# main.net
KiCad netlist of a schematic drawn in Altium Designer
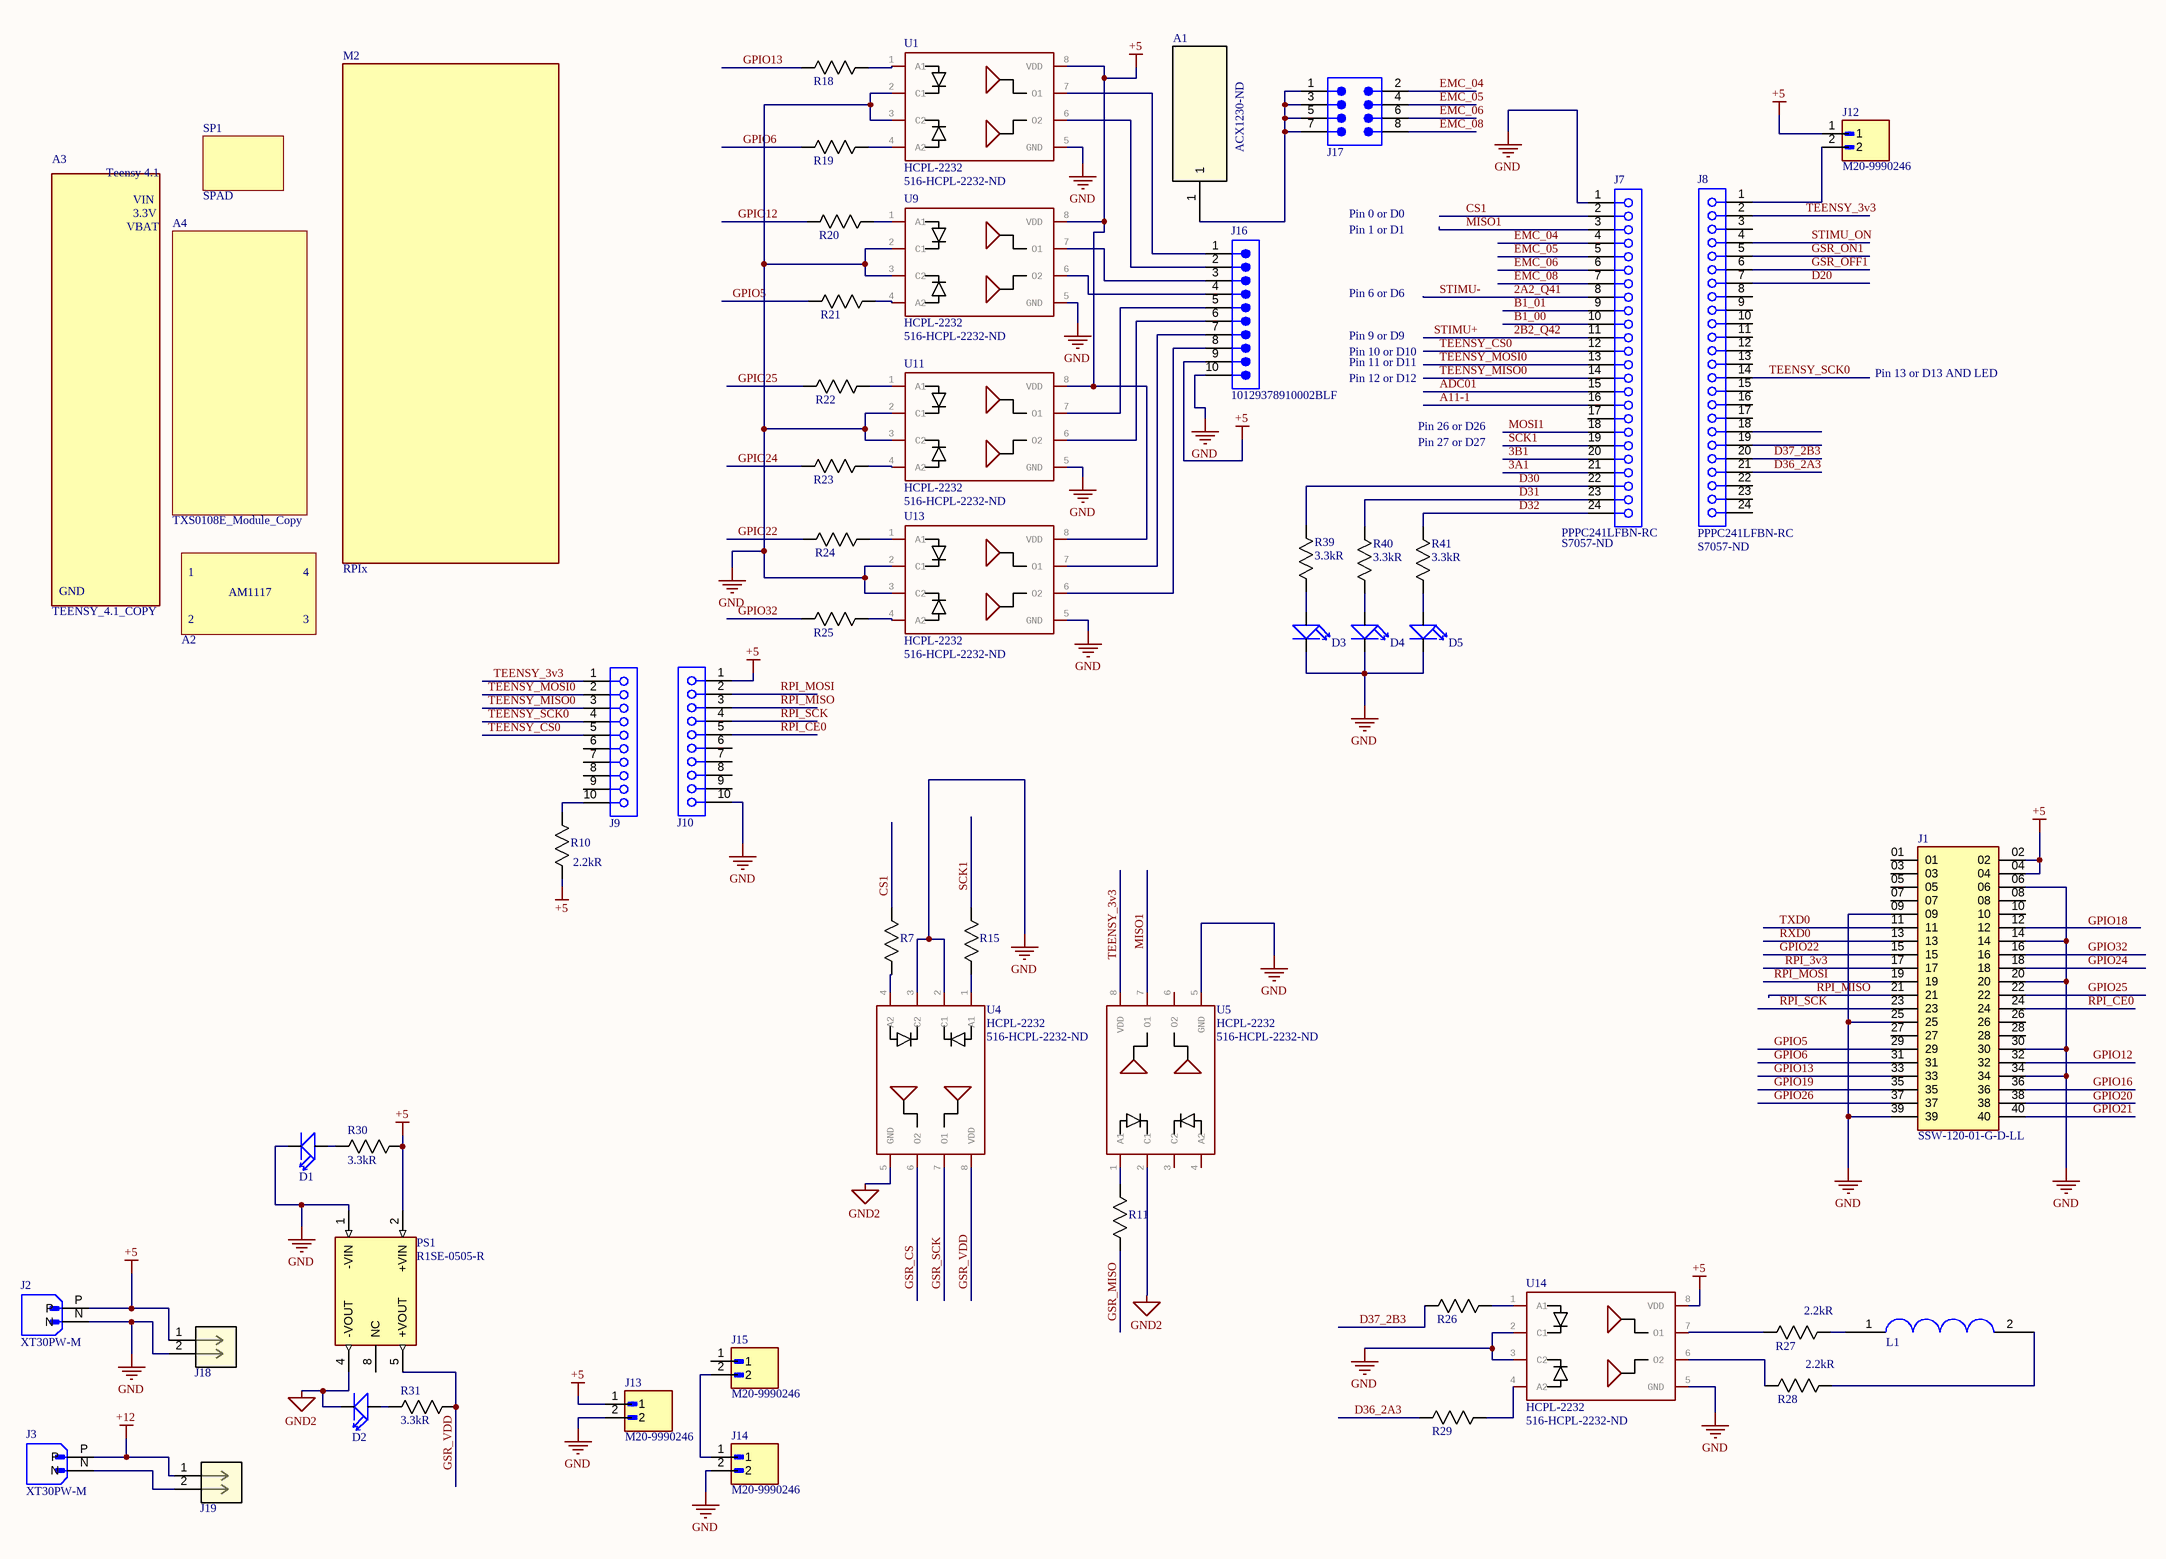
[diagram p0: main.SchDoc]

(export (version "E")
  (design (tool "Eeschema 10.0.6"))
  (components
    (comp (ref "A1")
      (value "SMA_VERTICAL")
      (footprint "SMA_VERTICAL")
      (description "connector, rf coaxial, sma str jack for p.c.board, 4 legs, .050 center cont, 50 ohm")
      (fields
        (field (name "MANUFACTURER") "Amphenol Connex")
        (field (name "MANUFACTURER PART NUMBER") "132134")
        (field (name "SUPPLIER PART NUMBER 1") "ACX1230-ND")
      )
      (libsource (lib "koncept") (part "SMA_VERTICAL"))
    )
    (comp (ref "A2")
      (value "AMS1117_BOARD_Copy")
      (footprint "AM117_BOARD_Copy")
      (libsource (lib "koncept") (part "AMS1117_BOARD_Copy"))
    )
    (comp (ref "A3")
      (value "TEENSY_4.1_COPY")
      (footprint "TEENSY_LONG_EXT_COPY")
      (fields (field (name "MF") "PJRC") (field (name "MP") "Teensy 4.1"))
      (libsource (lib "koncept") (part "TEENSY_4.1_COPY"))
    )
    (comp (ref "A4")
      (value "TXS0108E_Module_Copy")
      (footprint "TXS0108E_Module_Copy")
      (libsource (lib "koncept") (part "TXS0108E_Module_Copy"))
    )
    (comp (ref "D1")
      (value "LED")
      (footprint "LEDM1608X80")
      (description "Single Color LED, Ultra Bright Orange, Water Clear, 1.1mm")
      (fields
        (field (name "MANUFACTURER") "Vishay Lite-On")
        (field (name "MANUFACTURER PART NUMBER") "LTST-C190KFKT")
      )
      (libsource (lib "Passive") (part "LTST-C190KFKT_1"))
    )
    (comp (ref "D2")
      (value "LED")
      (footprint "LEDM1608X80")
      (description "Single Color LED, Ultra Bright Orange, Water Clear, 1.1mm")
      (fields
        (field (name "MANUFACTURER") "Vishay Lite-On")
        (field (name "MANUFACTURER PART NUMBER") "LTST-C190KFKT")
      )
      (libsource (lib "Passive") (part "LTST-C190KFKT_1"))
    )
    (comp (ref "D3")
      (value "LED")
      (footprint "LEDM1608X80")
      (description "Single Color LED, Ultra Bright Orange, Water Clear, 1.1mm")
      (fields
        (field (name "MANUFACTURER") "Vishay Lite-On")
        (field (name "MANUFACTURER PART NUMBER") "LTST-C190KFKT")
      )
      (libsource (lib "Passive") (part "LTST-C190KFKT_1"))
    )
    (comp (ref "D4")
      (value "LED")
      (footprint "LEDM1608X80")
      (description "Single Color LED, Ultra Bright Orange, Water Clear, 1.1mm")
      (fields
        (field (name "MANUFACTURER") "Vishay Lite-On")
        (field (name "MANUFACTURER PART NUMBER") "LTST-C190KFKT")
      )
      (libsource (lib "Passive") (part "LTST-C190KFKT_1"))
    )
    (comp (ref "D5")
      (value "LED")
      (footprint "LEDM1608X80")
      (description "Single Color LED, Ultra Bright Orange, Water Clear, 1.1mm")
      (fields
        (field (name "MANUFACTURER") "Vishay Lite-On")
        (field (name "MANUFACTURER PART NUMBER") "LTST-C190KFKT")
      )
      (libsource (lib "Passive") (part "LTST-C190KFKT_1"))
    )
    (comp (ref "J1")
      (value "SSW-120-01-G-D-LL")
      (footprint "SAMTEC_SSW-120-01-G-D-LL")
      (fields (field (name "MF") "Samtec Inc."))
      (libsource (lib "koncept") (part "SSW-120-01-G-D-LL"))
    )
    (comp (ref "J2")
      (value "XT30PW-M")
      (footprint "AMASS_XT30PW-M")
      (description "Socket; DC supply; XT30; male; PIN: 2; on PCBs; THT; Colour: yellow")
      (fields (field (name "MF") "AMASS"))
      (libsource (lib "koncept") (part "XT30PW-M"))
    )
    (comp (ref "J3")
      (value "XT30PW-M")
      (footprint "AMASS_XT30PW-M")
      (description "Socket; DC supply; XT30; male; PIN: 2; on PCBs; THT; Colour: yellow")
      (fields (field (name "MF") "AMASS"))
      (libsource (lib "koncept") (part "XT30PW-M"))
    )
    (comp (ref "J7")
      (value "PPPC241LFBN-RC")
      (footprint "HEADER_SOCKET_24")
      (description "Conn Hdr 24POS 0.1 Gold Pcb")
      (fields (field (name "MANUFACTURER") "Sullins") (field (name "SUPPLIER PART NUMBER 1") "S7057-ND"))
      (libsource (lib "Connectors") (part "HEADER_SOCKET_24"))
    )
    (comp (ref "J8")
      (value "PPPC241LFBN-RC")
      (footprint "HEADER_SOCKET_24")
      (description "Conn Hdr 24POS 0.1 Gold Pcb")
      (fields (field (name "MANUFACTURER") "Sullins") (field (name "SUPPLIER PART NUMBER 1") "S7057-ND"))
      (libsource (lib "Connectors") (part "HEADER_SOCKET_24"))
    )
    (comp (ref "J9")
      (value "PPTC101LFBN-RC")
      (footprint "HEADER_SOCKET_10")
      (description "10 Position Single Row 2.54 mm Pitch Vertical Through Hole Socket Header")
      (fields (field (name "MANUFACTURER") "Sullins"))
      (libsource (lib "Connectors") (part "HEADER_SOCKET_10"))
    )
    (comp (ref "J10")
      (value "PPTC101LFBN-RC")
      (footprint "HEADER_SOCKET_10")
      (description "10 Position Single Row 2.54 mm Pitch Vertical Through Hole Socket Header")
      (fields (field (name "MANUFACTURER") "Sullins"))
      (libsource (lib "Connectors") (part "HEADER_SOCKET_10"))
    )
    (comp (ref "J12")
      (value "M20-9990246")
      (footprint "HARWIN_M20-9990246")
      (description "2.54mm (0.1) Pitch SIL Vertical Throughboard Pin Header, 6.1mm mating pin height, tin, 2 contacts")
      (fields (field (name "MF") "Harwin"))
      (libsource (lib "koncept") (part "M20-9990246"))
    )
    (comp (ref "J13")
      (value "M20-9990246")
      (footprint "HARWIN_M20-9990246")
      (description "2.54mm (0.1) Pitch SIL Vertical Throughboard Pin Header, 6.1mm mating pin height, tin, 2 contacts")
      (fields (field (name "MF") "Harwin"))
      (libsource (lib "koncept") (part "M20-9990246"))
    )
    (comp (ref "J14")
      (value "M20-9990246")
      (footprint "HARWIN_M20-9990246")
      (description "2.54mm (0.1) Pitch SIL Vertical Throughboard Pin Header, 6.1mm mating pin height, tin, 2 contacts")
      (fields (field (name "MF") "Harwin"))
      (libsource (lib "koncept") (part "M20-9990246"))
    )
    (comp (ref "J15")
      (value "M20-9990246")
      (footprint "HARWIN_M20-9990246")
      (description "2.54mm (0.1) Pitch SIL Vertical Throughboard Pin Header, 6.1mm mating pin height, tin, 2 contacts")
      (fields (field (name "MF") "Harwin"))
      (libsource (lib "koncept") (part "M20-9990246"))
    )
    (comp (ref "J16")
      (value "10129378910002BLF")
      (footprint "HEADER_PIN_10")
      (description "Header Sr Vt Th 1X10-10129378-910002BLF")
      (fields (field (name "MANUFACTURER") "Amphenol ICC / FCI"))
      (libsource (lib "Connectors") (part "HEADER_PIN_10"))
    )
    (comp (ref "J17")
      (value "TSW-104-07-F-D")
      (footprint "HEADER_PIN_DOUBLE_8")
      (description "Connector, Header, 8Pos, 2Row, 2.54Mm Rohs Compliant: Yes")
      (fields (field (name "MANUFACTURER") "Samtec"))
      (libsource (lib "Connectors") (part "HEADER_PIN_DOUBLE_8"))
    )
    (comp (ref "J18")
      (value "B2P-VH")
      (footprint "CONN_B2P-VH_JST")
      (description "VH Non-RoHS Compliant 2003 Vertical Connector Header -25C~85C 10A 250V 0.303 7.70mm")
      (fields (field (name "MANUFACTURER") "JST"))
      (libsource (lib "Connectors") (part "B2P-VH"))
    )
    (comp (ref "J19")
      (value "B2P-VH")
      (footprint "CONN_B2P-VH_JST")
      (description "VH Non-RoHS Compliant 2003 Vertical Connector Header -25C~85C 10A 250V 0.303 7.70mm")
      (fields (field (name "MANUFACTURER") "JST"))
      (libsource (lib "Connectors") (part "B2P-VH"))
    )
    (comp (ref "L1")
      (value "COIL_PLANNER_A")
      (footprint "COIL_PLANNER_A")
      (libsource (lib "koncept") (part "COIL_PLANNER_A"))
    )
    (comp (ref "M2")
      (value "RPIx")
      (footprint "MODULE_RASPBERRY_PI_3_COPY")
      (libsource (lib "koncept") (part "RPIx_Copy"))
    )
    (comp (ref "PS1")
      (value "R1SE-0505-R")
      (footprint "CONV_R1SE-0505-R")
      (description "1W DC/DC-Converter 'ECONOLINE' SMD 1kV unreg")
      (fields (field (name "MF") "Recom Power"))
      (libsource (lib "koncept") (part "R1SE-0505-R"))
    )
    (comp (ref "R7")
      (value "RMCF1206FT220R")
      (footprint "STA_RMCF1206_STP-L")
      (description "No Description Available")
      (fields (field (name "COPYRIGHT") "Copyright (C) 2025 Ultra Librarian. All rights reserved."))
      (libsource (lib "Passive") (part "RMCF1206FT220R"))
    )
    (comp (ref "R10")
      (value "CRGCQ1206F2K2")
      (footprint "STA_RMCF1206_STP-L")
      (description "SMD Chip Resistor, 2.2 kOhm, ± 1%, 250 mW, 1206 [3216 Metric], Thick Film, General Purpose")
      (fields (field (name "MANUFACTURER") "TE Connectivity") (field (name "RESISTANCE") "2.2kR"))
      (libsource (lib "Passive") (part "R1206F2K2"))
    )
    (comp (ref "R11")
      (value "RMCF1206FT220R")
      (footprint "STA_RMCF1206_STP-L")
      (description "No Description Available")
      (fields (field (name "COPYRIGHT") "Copyright (C) 2025 Ultra Librarian. All rights reserved."))
      (libsource (lib "Passive") (part "RMCF1206FT220R"))
    )
    (comp (ref "R15")
      (value "RMCF1206FT220R")
      (footprint "STA_RMCF1206_STP-L")
      (description "No Description Available")
      (fields (field (name "COPYRIGHT") "Copyright (C) 2025 Ultra Librarian. All rights reserved."))
      (libsource (lib "Passive") (part "RMCF1206FT220R"))
    )
    (comp (ref "R18")
      (value "RMCF1206FT220R")
      (footprint "STA_RMCF1206_STP-L")
      (description "No Description Available")
      (fields (field (name "COPYRIGHT") "Copyright (C) 2025 Ultra Librarian. All rights reserved."))
      (libsource (lib "Passive") (part "RMCF1206FT220R"))
    )
    (comp (ref "R19")
      (value "RMCF1206FT220R")
      (footprint "STA_RMCF1206_STP-L")
      (description "No Description Available")
      (fields (field (name "COPYRIGHT") "Copyright (C) 2025 Ultra Librarian. All rights reserved."))
      (libsource (lib "Passive") (part "RMCF1206FT220R"))
    )
    (comp (ref "R20")
      (value "RMCF1206FT220R")
      (footprint "STA_RMCF1206_STP-L")
      (description "No Description Available")
      (fields (field (name "COPYRIGHT") "Copyright (C) 2025 Ultra Librarian. All rights reserved."))
      (libsource (lib "Passive") (part "RMCF1206FT220R"))
    )
    (comp (ref "R21")
      (value "RMCF1206FT220R")
      (footprint "STA_RMCF1206_STP-L")
      (description "No Description Available")
      (fields (field (name "COPYRIGHT") "Copyright (C) 2025 Ultra Librarian. All rights reserved."))
      (libsource (lib "Passive") (part "RMCF1206FT220R"))
    )
    (comp (ref "R22")
      (value "RMCF1206FT220R")
      (footprint "STA_RMCF1206_STP-L")
      (description "No Description Available")
      (fields (field (name "COPYRIGHT") "Copyright (C) 2025 Ultra Librarian. All rights reserved."))
      (libsource (lib "Passive") (part "RMCF1206FT220R"))
    )
    (comp (ref "R23")
      (value "RMCF1206FT220R")
      (footprint "STA_RMCF1206_STP-L")
      (description "No Description Available")
      (fields (field (name "COPYRIGHT") "Copyright (C) 2025 Ultra Librarian. All rights reserved."))
      (libsource (lib "Passive") (part "RMCF1206FT220R"))
    )
    (comp (ref "R24")
      (value "RMCF1206FT220R")
      (footprint "STA_RMCF1206_STP-L")
      (description "No Description Available")
      (fields (field (name "COPYRIGHT") "Copyright (C) 2025 Ultra Librarian. All rights reserved."))
      (libsource (lib "Passive") (part "RMCF1206FT220R"))
    )
    (comp (ref "R25")
      (value "RMCF1206FT220R")
      (footprint "STA_RMCF1206_STP-L")
      (description "No Description Available")
      (fields (field (name "COPYRIGHT") "Copyright (C) 2025 Ultra Librarian. All rights reserved."))
      (libsource (lib "Passive") (part "RMCF1206FT220R"))
    )
    (comp (ref "R26")
      (value "RMCF1206FT220R")
      (footprint "STA_RMCF1206_STP-L")
      (description "No Description Available")
      (fields (field (name "COPYRIGHT") "Copyright (C) 2025 Ultra Librarian. All rights reserved."))
      (libsource (lib "Passive") (part "RMCF1206FT220R"))
    )
    (comp (ref "R27")
      (value "CRGCQ1206F2K2")
      (footprint "STA_RMCF1206_STP-L")
      (description "SMD Chip Resistor, 2.2 kOhm, ± 1%, 250 mW, 1206 [3216 Metric], Thick Film, General Purpose")
      (fields (field (name "MANUFACTURER") "TE Connectivity") (field (name "RESISTANCE") "2.2kR"))
      (libsource (lib "Passive") (part "R1206F2K2"))
    )
    (comp (ref "R28")
      (value "CRGCQ1206F2K2")
      (footprint "STA_RMCF1206_STP-L")
      (description "SMD Chip Resistor, 2.2 kOhm, ± 1%, 250 mW, 1206 [3216 Metric], Thick Film, General Purpose")
      (fields (field (name "MANUFACTURER") "TE Connectivity") (field (name "RESISTANCE") "2.2kR"))
      (libsource (lib "Passive") (part "R1206F2K2"))
    )
    (comp (ref "R29")
      (value "RMCF1206FT220R")
      (footprint "STA_RMCF1206_STP-L")
      (description "No Description Available")
      (fields (field (name "COPYRIGHT") "Copyright (C) 2025 Ultra Librarian. All rights reserved."))
      (libsource (lib "Passive") (part "RMCF1206FT220R"))
    )
    (comp (ref "R30")
      (value "CRG1206F3K3")
      (footprint "STA_RMCF1206_STP-L")
      (description "Res Thick Film 1206 3.3K Ohm 1% 0.25W(1/4W) ±100ppm/C Pad SMD T/R")
      (fields
        (field (name "MANUFACTURER") "TE Connectivity")
        (field (name "TOLERANCE") "1%")
        (field (name "RESISTANCE") "3.3kR")
      )
      (libsource (lib "Passive") (part "R3K3_1206"))
    )
    (comp (ref "R31")
      (value "CRG1206F3K3")
      (footprint "STA_RMCF1206_STP-L")
      (description "Res Thick Film 1206 3.3K Ohm 1% 0.25W(1/4W) ±100ppm/C Pad SMD T/R")
      (fields
        (field (name "MANUFACTURER") "TE Connectivity")
        (field (name "TOLERANCE") "1%")
        (field (name "RESISTANCE") "3.3kR")
      )
      (libsource (lib "Passive") (part "R3K3_1206"))
    )
    (comp (ref "R39")
      (value "CRG1206F3K3")
      (footprint "STA_RMCF1206_STP-L")
      (description "Res Thick Film 1206 3.3K Ohm 1% 0.25W(1/4W) ±100ppm/C Pad SMD T/R")
      (fields
        (field (name "MANUFACTURER") "TE Connectivity")
        (field (name "TOLERANCE") "1%")
        (field (name "RESISTANCE") "3.3kR")
      )
      (libsource (lib "Passive") (part "R3K3_1206"))
    )
    (comp (ref "R40")
      (value "CRG1206F3K3")
      (footprint "STA_RMCF1206_STP-L")
      (description "Res Thick Film 1206 3.3K Ohm 1% 0.25W(1/4W) ±100ppm/C Pad SMD T/R")
      (fields
        (field (name "MANUFACTURER") "TE Connectivity")
        (field (name "TOLERANCE") "1%")
        (field (name "RESISTANCE") "3.3kR")
      )
      (libsource (lib "Passive") (part "R3K3_1206"))
    )
    (comp (ref "R41")
      (value "CRG1206F3K3")
      (footprint "STA_RMCF1206_STP-L")
      (description "Res Thick Film 1206 3.3K Ohm 1% 0.25W(1/4W) ±100ppm/C Pad SMD T/R")
      (fields
        (field (name "MANUFACTURER") "TE Connectivity")
        (field (name "TOLERANCE") "1%")
        (field (name "RESISTANCE") "3.3kR")
      )
      (libsource (lib "Passive") (part "R3K3_1206"))
    )
    (comp (ref "SP1") (value "SPAD") (footprint "SPAD") (libsource (lib "koncept") (part "SPAD")))
    (comp (ref "U1")
      (value "HCPL-2232")
      (footprint "DIL08")
      (description "Optocoupler Logic Output Totem-Pole DC Input 2 Channel 8-Pin Plastic Dip Tube")
      (fields
        (field (name "MANUFACTURER") "Broadcom Avago")
        (field (name "SUPPLIER PART NUMBER 1") "516-HCPL-2232-ND")
      )
      (libsource (lib "koncept") (part "HCPL-2232"))
    )
    (comp (ref "U4")
      (value "HCPL-2232")
      (footprint "DIL08")
      (description "Optocoupler Logic Output Totem-Pole DC Input 2 Channel 8-Pin Plastic Dip Tube")
      (fields
        (field (name "MANUFACTURER") "Broadcom Avago")
        (field (name "SUPPLIER PART NUMBER 1") "516-HCPL-2232-ND")
      )
      (libsource (lib "koncept") (part "HCPL-2232"))
    )
    (comp (ref "U5")
      (value "HCPL-2232")
      (footprint "DIL08")
      (description "Optocoupler Logic Output Totem-Pole DC Input 2 Channel 8-Pin Plastic Dip Tube")
      (fields
        (field (name "MANUFACTURER") "Broadcom Avago")
        (field (name "SUPPLIER PART NUMBER 1") "516-HCPL-2232-ND")
      )
      (libsource (lib "koncept") (part "HCPL-2232"))
    )
    (comp (ref "U9")
      (value "HCPL-2232")
      (footprint "DIL08")
      (description "Optocoupler Logic Output Totem-Pole DC Input 2 Channel 8-Pin Plastic Dip Tube")
      (fields
        (field (name "MANUFACTURER") "Broadcom Avago")
        (field (name "SUPPLIER PART NUMBER 1") "516-HCPL-2232-ND")
      )
      (libsource (lib "koncept") (part "HCPL-2232"))
    )
    (comp (ref "U11")
      (value "HCPL-2232")
      (footprint "DIL08")
      (description "Optocoupler Logic Output Totem-Pole DC Input 2 Channel 8-Pin Plastic Dip Tube")
      (fields
        (field (name "MANUFACTURER") "Broadcom Avago")
        (field (name "SUPPLIER PART NUMBER 1") "516-HCPL-2232-ND")
      )
      (libsource (lib "koncept") (part "HCPL-2232"))
    )
    (comp (ref "U13")
      (value "HCPL-2232")
      (footprint "DIL08")
      (description "Optocoupler Logic Output Totem-Pole DC Input 2 Channel 8-Pin Plastic Dip Tube")
      (fields
        (field (name "MANUFACTURER") "Broadcom Avago")
        (field (name "SUPPLIER PART NUMBER 1") "516-HCPL-2232-ND")
      )
      (libsource (lib "koncept") (part "HCPL-2232"))
    )
    (comp (ref "U14")
      (value "HCPL-2232")
      (footprint "DIL08")
      (description "Optocoupler Logic Output Totem-Pole DC Input 2 Channel 8-Pin Plastic Dip Tube")
      (fields
        (field (name "MANUFACTURER") "Broadcom Avago")
        (field (name "SUPPLIER PART NUMBER 1") "516-HCPL-2232-ND")
      )
      (libsource (lib "koncept") (part "HCPL-2232"))
    )
  )
  (nets
    (net (code "1") (name "+5") (class "Default")
      (node (ref "J1") (pin "02") (pinfunction "02_02") (pintype "passive"))
      (node (ref "J1") (pin "04") (pinfunction "04_04") (pintype "passive"))
      (node (ref "J10") (pin "1") (pinfunction "1_1") (pintype "passive"))
      (node (ref "J12") (pin "1") (pinfunction "1_1") (pintype "passive"))
      (node (ref "J13") (pin "1") (pinfunction "1_1") (pintype "passive"))
      (node (ref "J16") (pin "9") (pinfunction "9_9") (pintype "passive"))
      (node (ref "J18") (pin "1") (pinfunction "1_1") (pintype "passive"))
      (node (ref "J2") (pin "P") (pinfunction "P_P") (pintype "power_in"))
      (node (ref "PS1") (pin "2") (pinfunction "+VIN_2") (pintype "input"))
      (node (ref "R10") (pin "1") (pinfunction "1_1") (pintype "passive"))
      (node (ref "R30") (pin "2") (pinfunction "2_2") (pintype "passive"))
      (node (ref "U1") (pin "8") (pinfunction "VDD_8") (pintype "power_in"))
      (node (ref "U11") (pin "8") (pinfunction "VDD_8") (pintype "power_in"))
      (node (ref "U13") (pin "8") (pinfunction "VDD_8") (pintype "power_in"))
      (node (ref "U14") (pin "8") (pinfunction "VDD_8") (pintype "power_in"))
      (node (ref "U9") (pin "8") (pinfunction "VDD_8") (pintype "power_in"))
    )
    (net (code "2") (name "+12") (class "Default")
      (node (ref "J19") (pin "1") (pinfunction "1_1") (pintype "passive"))
      (node (ref "J3") (pin "P") (pinfunction "P_P") (pintype "power_in"))
    )
    (net (code "3") (name "/2A2_Q41") (class "Default")
      (node (ref "J7") (pin "8") (pinfunction "8_8") (pintype "passive"))
    )
    (net (code "4") (name "/2B2_Q42") (class "Default")
      (node (ref "J7") (pin "11") (pinfunction "11_11") (pintype "passive"))
    )
    (net (code "5") (name "/3A1") (class "Default")
      (node (ref "J7") (pin "21") (pinfunction "21_21") (pintype "passive"))
    )
    (net (code "6") (name "/3B1") (class "Default")
      (node (ref "J7") (pin "20") (pinfunction "20_20") (pintype "passive"))
    )
    (net (code "7") (name "/A11-1") (class "Default")
      (node (ref "J7") (pin "16") (pinfunction "16_16") (pintype "passive"))
    )
    (net (code "8") (name "/ADC01") (class "Default")
      (node (ref "J7") (pin "15") (pinfunction "15_15") (pintype "passive"))
    )
    (net (code "9") (name "/B1_00") (class "Default")
      (node (ref "J7") (pin "10") (pinfunction "10_10") (pintype "passive"))
    )
    (net (code "10") (name "/B1_01") (class "Default")
      (node (ref "J7") (pin "9") (pinfunction "9_9") (pintype "passive"))
    )
    (net (code "11") (name "/CS1") (class "Default")
      (node (ref "J7") (pin "2") (pinfunction "2_2") (pintype "passive"))
      (node (ref "R7") (pin "2") (pinfunction "2_2") (pintype "passive"))
    )
    (net (code "12") (name "/D20") (class "Default")
      (node (ref "J8") (pin "7") (pinfunction "7_7") (pintype "passive"))
    )
    (net (code "13") (name "/D30") (class "Default")
      (node (ref "J7") (pin "22") (pinfunction "22_22") (pintype "passive"))
      (node (ref "R39") (pin "2") (pinfunction "2_2") (pintype "passive"))
    )
    (net (code "14") (name "/D31") (class "Default")
      (node (ref "J7") (pin "23") (pinfunction "23_23") (pintype "passive"))
      (node (ref "R40") (pin "2") (pinfunction "2_2") (pintype "passive"))
    )
    (net (code "15") (name "/D32") (class "Default")
      (node (ref "J7") (pin "24") (pinfunction "24_24") (pintype "passive"))
      (node (ref "R41") (pin "2") (pinfunction "2_2") (pintype "passive"))
    )
    (net (code "16") (name "/D36_2A3") (class "Default")
      (node (ref "J8") (pin "21") (pinfunction "21_21") (pintype "passive"))
      (node (ref "R29") (pin "2") (pinfunction "2_2") (pintype "passive"))
    )
    (net (code "17") (name "/D37_2B3") (class "Default")
      (node (ref "J8") (pin "20") (pinfunction "20_20") (pintype "passive"))
      (node (ref "R26") (pin "2") (pinfunction "2_2") (pintype "passive"))
    )
    (net (code "18") (name "/EMC_04") (class "Default")
      (node (ref "J17") (pin "2") (pinfunction "2_2") (pintype "passive"))
      (node (ref "J7") (pin "4") (pinfunction "4_4") (pintype "passive"))
    )
    (net (code "19") (name "/EMC_05") (class "Default")
      (node (ref "J17") (pin "4") (pinfunction "4_4") (pintype "passive"))
      (node (ref "J7") (pin "5") (pinfunction "5_5") (pintype "passive"))
    )
    (net (code "20") (name "/EMC_06") (class "Default")
      (node (ref "J17") (pin "6") (pinfunction "6_6") (pintype "passive"))
      (node (ref "J7") (pin "6") (pinfunction "6_6") (pintype "passive"))
    )
    (net (code "21") (name "/EMC_08") (class "Default")
      (node (ref "J17") (pin "8") (pinfunction "8_8") (pintype "passive"))
      (node (ref "J7") (pin "7") (pinfunction "7_7") (pintype "passive"))
    )
    (net (code "22") (name "/GPIO5") (class "Default")
      (node (ref "J1") (pin "29") (pinfunction "29_29") (pintype "passive"))
      (node (ref "R21") (pin "2") (pinfunction "2_2") (pintype "passive"))
    )
    (net (code "23") (name "/GPIO6") (class "Default")
      (node (ref "J1") (pin "31") (pinfunction "31_31") (pintype "passive"))
      (node (ref "R19") (pin "2") (pinfunction "2_2") (pintype "passive"))
    )
    (net (code "24") (name "/GPIO12") (class "Default")
      (node (ref "J1") (pin "32") (pinfunction "32_32") (pintype "passive"))
      (node (ref "R20") (pin "2") (pinfunction "2_2") (pintype "passive"))
    )
    (net (code "25") (name "/GPIO13") (class "Default")
      (node (ref "J1") (pin "33") (pinfunction "33_33") (pintype "passive"))
      (node (ref "R18") (pin "2") (pinfunction "2_2") (pintype "passive"))
    )
    (net (code "26") (name "/GPIO16") (class "Default")
      (node (ref "J1") (pin "36") (pinfunction "36_36") (pintype "passive"))
    )
    (net (code "28") (name "/GPIO19") (class "Default")
      (node (ref "J1") (pin "35") (pinfunction "35_35") (pintype "passive"))
    )
    (net (code "30") (name "/GPIO21") (class "Default")
      (node (ref "J1") (pin "40") (pinfunction "40_40") (pintype "passive"))
    )
    (net (code "31") (name "/GPIO22") (class "Default")
      (node (ref "J1") (pin "15") (pinfunction "15_15") (pintype "passive"))
      (node (ref "R24") (pin "2") (pinfunction "2_2") (pintype "passive"))
    )
    (net (code "32") (name "/GPIO24") (class "Default")
      (node (ref "J1") (pin "18") (pinfunction "18_18") (pintype "passive"))
      (node (ref "R23") (pin "2") (pinfunction "2_2") (pintype "passive"))
    )
    (net (code "33") (name "/GPIO25") (class "Default")
      (node (ref "J1") (pin "22") (pinfunction "22_22") (pintype "passive"))
      (node (ref "R22") (pin "2") (pinfunction "2_2") (pintype "passive"))
    )
    (net (code "34") (name "/GPIO26") (class "Default")
      (node (ref "J1") (pin "37") (pinfunction "37_37") (pintype "passive"))
    )
    (net (code "35") (name "/GPIO32") (class "Default")
      (node (ref "J1") (pin "16") (pinfunction "16_16") (pintype "passive"))
      (node (ref "R25") (pin "2") (pinfunction "2_2") (pintype "passive"))
    )
    (net (code "36") (name "/GSR_CS") (class "Default")
      (node (ref "U4") (pin "6") (pinfunction "O2_6") (pintype "power_in"))
    )
    (net (code "37") (name "/GSR_MISO") (class "Default")
      (node (ref "R11") (pin "1") (pinfunction "1_1") (pintype "passive"))
    )
    (net (code "38") (name "/GSR_OFF1") (class "Default")
      (node (ref "J8") (pin "6") (pinfunction "6_6") (pintype "passive"))
    )
    (net (code "39") (name "/GSR_ON1") (class "Default")
      (node (ref "J8") (pin "5") (pinfunction "5_5") (pintype "passive"))
    )
    (net (code "40") (name "/GSR_SCK") (class "Default")
      (node (ref "U4") (pin "7") (pinfunction "O1_7") (pintype "power_in"))
    )
    (net (code "41") (name "/GSR_VDD") (class "Default")
      (node (ref "PS1") (pin "5") (pinfunction "+VOUT_5") (pintype "output"))
      (node (ref "R31") (pin "2") (pinfunction "2_2") (pintype "passive"))
      (node (ref "U4") (pin "8") (pinfunction "VDD_8") (pintype "power_in"))
    )
    (net (code "42") (name "/MISO1") (class "Default")
      (node (ref "J7") (pin "3") (pinfunction "3_3") (pintype "passive"))
      (node (ref "U5") (pin "7") (pinfunction "O1_7") (pintype "power_in"))
    )
    (net (code "43") (name "/MOSI1") (class "Default")
      (node (ref "J7") (pin "18") (pinfunction "18_18") (pintype "passive"))
    )
    (net (code "44") (name "/RPI_3v3") (class "Default")
      (node (ref "J1") (pin "17") (pinfunction "17_17") (pintype "passive"))
    )
    (net (code "45") (name "/RPI_CE0") (class "Default")
      (node (ref "J1") (pin "24") (pinfunction "24_24") (pintype "passive"))
      (node (ref "J10") (pin "5") (pinfunction "5_5") (pintype "passive"))
    )
    (net (code "46") (name "/RPI_MISO") (class "Default")
      (node (ref "J1") (pin "21") (pinfunction "21_21") (pintype "passive"))
      (node (ref "J10") (pin "3") (pinfunction "3_3") (pintype "passive"))
    )
    (net (code "47") (name "/RPI_MOSI") (class "Default")
      (node (ref "J1") (pin "19") (pinfunction "19_19") (pintype "passive"))
      (node (ref "J10") (pin "2") (pinfunction "2_2") (pintype "passive"))
    )
    (net (code "48") (name "/RPI_SCK") (class "Default")
      (node (ref "J1") (pin "23") (pinfunction "23_23") (pintype "passive"))
      (node (ref "J10") (pin "4") (pinfunction "4_4") (pintype "passive"))
    )
    (net (code "49") (name "/RXD0") (class "Default")
      (node (ref "J1") (pin "13") (pinfunction "13_13") (pintype "passive"))
    )
    (net (code "50") (name "/SCK1") (class "Default")
      (node (ref "J7") (pin "19") (pinfunction "19_19") (pintype "passive"))
      (node (ref "R15") (pin "2") (pinfunction "2_2") (pintype "passive"))
    )
    (net (code "51") (name "/STIMU_ON") (class "Default")
      (node (ref "J8") (pin "4") (pinfunction "4_4") (pintype "passive"))
    )
    (net (code "52") (name "/TEENSY_3v3") (class "Default")
      (node (ref "J8") (pin "2") (pinfunction "2_2") (pintype "passive"))
      (node (ref "J9") (pin "1") (pinfunction "1_1") (pintype "passive"))
      (node (ref "U5") (pin "8") (pinfunction "VDD_8") (pintype "power_in"))
    )
    (net (code "53") (name "/TEENSY_CS0") (class "Default")
      (node (ref "J7") (pin "12") (pinfunction "12_12") (pintype "passive"))
      (node (ref "J9") (pin "5") (pinfunction "5_5") (pintype "passive"))
    )
    (net (code "54") (name "/TEENSY_MISO0") (class "Default")
      (node (ref "J7") (pin "14") (pinfunction "14_14") (pintype "passive"))
      (node (ref "J9") (pin "3") (pinfunction "3_3") (pintype "passive"))
    )
    (net (code "55") (name "/TEENSY_MOSI0") (class "Default")
      (node (ref "J7") (pin "13") (pinfunction "13_13") (pintype "passive"))
      (node (ref "J9") (pin "2") (pinfunction "2_2") (pintype "passive"))
    )
    (net (code "56") (name "/TEENSY_SCK0") (class "Default")
      (node (ref "J8") (pin "14") (pinfunction "14_14") (pintype "passive"))
      (node (ref "J9") (pin "4") (pinfunction "4_4") (pintype "passive"))
    )
    (net (code "57") (name "/TXD0") (class "Default")
      (node (ref "J1") (pin "11") (pinfunction "11_11") (pintype "passive"))
    )
    (net (code "58") (name "GND") (class "Default")
      (node (ref "D1") (pin "C") (pinfunction "C_C") (pintype "passive"))
      (node (ref "D3") (pin "C") (pinfunction "C_C") (pintype "passive"))
      (node (ref "D4") (pin "C") (pinfunction "C_C") (pintype "passive"))
      (node (ref "D5") (pin "C") (pinfunction "C_C") (pintype "passive"))
      (node (ref "J1") (pin "06") (pinfunction "06_06") (pintype "passive"))
      (node (ref "J1") (pin "09") (pinfunction "09_09") (pintype "passive"))
      (node (ref "J1") (pin "14") (pinfunction "14_14") (pintype "passive"))
      (node (ref "J1") (pin "20") (pinfunction "20_20") (pintype "passive"))
      (node (ref "J1") (pin "25") (pinfunction "25_25") (pintype "passive"))
      (node (ref "J1") (pin "30") (pinfunction "30_30") (pintype "passive"))
      (node (ref "J1") (pin "34") (pinfunction "34_34") (pintype "passive"))
      (node (ref "J1") (pin "39") (pinfunction "39_39") (pintype "passive"))
      (node (ref "J10") (pin "10") (pinfunction "10_10") (pintype "passive"))
      (node (ref "J13") (pin "2") (pinfunction "2_2") (pintype "passive"))
      (node (ref "J14") (pin "2") (pinfunction "2_2") (pintype "passive"))
      (node (ref "J16") (pin "10") (pinfunction "10_10") (pintype "passive"))
      (node (ref "J18") (pin "2") (pinfunction "2_2") (pintype "passive"))
      (node (ref "J2") (pin "N") (pinfunction "N_N") (pintype "power_in"))
      (node (ref "J7") (pin "1") (pinfunction "1_1") (pintype "passive"))
      (node (ref "PS1") (pin "1") (pinfunction "-VIN_1") (pintype "input"))
      (node (ref "U1") (pin "2") (pinfunction "C1_2") (pintype "power_in"))
      (node (ref "U1") (pin "3") (pinfunction "C2_3") (pintype "power_in"))
      (node (ref "U1") (pin "5") (pinfunction "GND_5") (pintype "power_in"))
      (node (ref "U11") (pin "2") (pinfunction "C1_2") (pintype "power_in"))
      (node (ref "U11") (pin "3") (pinfunction "C2_3") (pintype "power_in"))
      (node (ref "U11") (pin "5") (pinfunction "GND_5") (pintype "power_in"))
      (node (ref "U13") (pin "2") (pinfunction "C1_2") (pintype "power_in"))
      (node (ref "U13") (pin "3") (pinfunction "C2_3") (pintype "power_in"))
      (node (ref "U13") (pin "5") (pinfunction "GND_5") (pintype "power_in"))
      (node (ref "U14") (pin "2") (pinfunction "C1_2") (pintype "power_in"))
      (node (ref "U14") (pin "3") (pinfunction "C2_3") (pintype "power_in"))
      (node (ref "U14") (pin "5") (pinfunction "GND_5") (pintype "power_in"))
      (node (ref "U4") (pin "2") (pinfunction "C1_2") (pintype "power_in"))
      (node (ref "U4") (pin "3") (pinfunction "C2_3") (pintype "power_in"))
      (node (ref "U5") (pin "5") (pinfunction "GND_5") (pintype "power_in"))
      (node (ref "U9") (pin "2") (pinfunction "C1_2") (pintype "power_in"))
      (node (ref "U9") (pin "3") (pinfunction "C2_3") (pintype "power_in"))
      (node (ref "U9") (pin "5") (pinfunction "GND_5") (pintype "power_in"))
    )
    (net (code "59") (name "GND2") (class "Default")
      (node (ref "D2") (pin "C") (pinfunction "C_C") (pintype "passive"))
      (node (ref "PS1") (pin "4") (pinfunction "-VOUT_4") (pintype "output"))
      (node (ref "U4") (pin "5") (pinfunction "GND_5") (pintype "power_in"))
      (node (ref "U5") (pin "2") (pinfunction "C1_2") (pintype "power_in"))
    )
    (net (code "60") (name "Net-(A1-Pad1)") (class "Default")
      (node (ref "A1") (pin "1") (pinfunction "1_1") (pintype "passive"))
      (node (ref "J17") (pin "1") (pinfunction "1_1") (pintype "passive"))
      (node (ref "J17") (pin "3") (pinfunction "3_3") (pintype "passive"))
      (node (ref "J17") (pin "5") (pinfunction "5_5") (pintype "passive"))
      (node (ref "J17") (pin "7") (pinfunction "7_7") (pintype "passive"))
    )
    (net (code "61") (name "Net-(D1-PadA)") (class "Default")
      (node (ref "D1") (pin "A") (pinfunction "A_A") (pintype "passive"))
      (node (ref "R30") (pin "1") (pinfunction "1_1") (pintype "passive"))
    )
    (net (code "62") (name "Net-(D2-PadA)") (class "Default")
      (node (ref "D2") (pin "A") (pinfunction "A_A") (pintype "passive"))
      (node (ref "R31") (pin "1") (pinfunction "1_1") (pintype "passive"))
    )
    (net (code "63") (name "Net-(D3-PadA)") (class "Default")
      (node (ref "D3") (pin "A") (pinfunction "A_A") (pintype "passive"))
      (node (ref "R39") (pin "1") (pinfunction "1_1") (pintype "passive"))
    )
    (net (code "64") (name "Net-(D4-PadA)") (class "Default")
      (node (ref "D4") (pin "A") (pinfunction "A_A") (pintype "passive"))
      (node (ref "R40") (pin "1") (pinfunction "1_1") (pintype "passive"))
    )
    (net (code "65") (name "Net-(D5-PadA)") (class "Default")
      (node (ref "D5") (pin "A") (pinfunction "A_A") (pintype "passive"))
      (node (ref "R41") (pin "1") (pinfunction "1_1") (pintype "passive"))
    )
    (net (code "66") (name "Net-(J9-Pad10)") (class "Default")
      (node (ref "J9") (pin "10") (pinfunction "10_10") (pintype "passive"))
      (node (ref "R10") (pin "2") (pinfunction "2_2") (pintype "passive"))
    )
    (net (code "67") (name "Net-(J12-Pad2)") (class "Default")
      (node (ref "J12") (pin "2") (pinfunction "2_2") (pintype "passive"))
      (node (ref "J8") (pin "1") (pinfunction "1_1") (pintype "passive"))
    )
    (net (code "68") (name "Net-(J14-Pad1)") (class "Default")
      (node (ref "J14") (pin "1") (pinfunction "1_1") (pintype "passive"))
      (node (ref "J15") (pin "2") (pinfunction "2_2") (pintype "passive"))
    )
    (net (code "69") (name "Net-(J19-Pad2)") (class "Default")
      (node (ref "J19") (pin "2") (pinfunction "2_2") (pintype "passive"))
      (node (ref "J3") (pin "N") (pinfunction "N_N") (pintype "power_in"))
    )
    (net (code "70") (name "Net-(L1-Pad1)") (class "Default")
      (node (ref "L1") (pin "1") (pinfunction "1_1") (pintype "passive"))
      (node (ref "R27") (pin "2") (pinfunction "2_2") (pintype "passive"))
    )
    (net (code "71") (name "Net-(L1-Pad2)") (class "Default")
      (node (ref "L1") (pin "2") (pinfunction "2_2") (pintype "passive"))
      (node (ref "R28") (pin "2") (pinfunction "2_2") (pintype "passive"))
    )
    (net (code "72") (name "Net-(U1-A1)") (class "Default")
      (node (ref "R18") (pin "1") (pinfunction "1_1") (pintype "passive"))
      (node (ref "U1") (pin "1") (pinfunction "A1_1") (pintype "power_in"))
    )
    (net (code "73") (name "Net-(U1-A2)") (class "Default")
      (node (ref "R19") (pin "1") (pinfunction "1_1") (pintype "passive"))
      (node (ref "U1") (pin "4") (pinfunction "A2_4") (pintype "power_in"))
    )
    (net (code "74") (name "Net-(U1-O1)") (class "Default")
      (node (ref "J16") (pin "1") (pinfunction "1_1") (pintype "passive"))
      (node (ref "U1") (pin "7") (pinfunction "O1_7") (pintype "power_in"))
    )
    (net (code "75") (name "Net-(U1-O2)") (class "Default")
      (node (ref "J16") (pin "2") (pinfunction "2_2") (pintype "passive"))
      (node (ref "U1") (pin "6") (pinfunction "O2_6") (pintype "power_in"))
    )
    (net (code "76") (name "Net-(U4-A1)") (class "Default")
      (node (ref "R15") (pin "1") (pinfunction "1_1") (pintype "passive"))
      (node (ref "U4") (pin "1") (pinfunction "A1_1") (pintype "power_in"))
    )
    (net (code "77") (name "Net-(U4-A2)") (class "Default")
      (node (ref "R7") (pin "1") (pinfunction "1_1") (pintype "passive"))
      (node (ref "U4") (pin "4") (pinfunction "A2_4") (pintype "power_in"))
    )
    (net (code "78") (name "Net-(U5-A1)") (class "Default")
      (node (ref "R11") (pin "2") (pinfunction "2_2") (pintype "passive"))
      (node (ref "U5") (pin "1") (pinfunction "A1_1") (pintype "power_in"))
    )
    (net (code "79") (name "Net-(U9-A1)") (class "Default")
      (node (ref "R20") (pin "1") (pinfunction "1_1") (pintype "passive"))
      (node (ref "U9") (pin "1") (pinfunction "A1_1") (pintype "power_in"))
    )
    (net (code "80") (name "Net-(U9-A2)") (class "Default")
      (node (ref "R21") (pin "1") (pinfunction "1_1") (pintype "passive"))
      (node (ref "U9") (pin "4") (pinfunction "A2_4") (pintype "power_in"))
    )
    (net (code "81") (name "Net-(U9-O1)") (class "Default")
      (node (ref "J16") (pin "3") (pinfunction "3_3") (pintype "passive"))
      (node (ref "U9") (pin "7") (pinfunction "O1_7") (pintype "power_in"))
    )
    (net (code "82") (name "Net-(U9-O2)") (class "Default")
      (node (ref "J16") (pin "4") (pinfunction "4_4") (pintype "passive"))
      (node (ref "U9") (pin "6") (pinfunction "O2_6") (pintype "power_in"))
    )
    (net (code "83") (name "Net-(U11-A1)") (class "Default")
      (node (ref "R22") (pin "1") (pinfunction "1_1") (pintype "passive"))
      (node (ref "U11") (pin "1") (pinfunction "A1_1") (pintype "power_in"))
    )
    (net (code "84") (name "Net-(U11-A2)") (class "Default")
      (node (ref "R23") (pin "1") (pinfunction "1_1") (pintype "passive"))
      (node (ref "U11") (pin "4") (pinfunction "A2_4") (pintype "power_in"))
    )
    (net (code "85") (name "Net-(U11-O1)") (class "Default")
      (node (ref "J16") (pin "5") (pinfunction "5_5") (pintype "passive"))
      (node (ref "U11") (pin "7") (pinfunction "O1_7") (pintype "power_in"))
    )
    (net (code "86") (name "Net-(U11-O2)") (class "Default")
      (node (ref "J16") (pin "6") (pinfunction "6_6") (pintype "passive"))
      (node (ref "U11") (pin "6") (pinfunction "O2_6") (pintype "power_in"))
    )
    (net (code "87") (name "Net-(U13-A1)") (class "Default")
      (node (ref "R24") (pin "1") (pinfunction "1_1") (pintype "passive"))
      (node (ref "U13") (pin "1") (pinfunction "A1_1") (pintype "power_in"))
    )
    (net (code "88") (name "Net-(U13-A2)") (class "Default")
      (node (ref "R25") (pin "1") (pinfunction "1_1") (pintype "passive"))
      (node (ref "U13") (pin "4") (pinfunction "A2_4") (pintype "power_in"))
    )
    (net (code "89") (name "Net-(U13-O1)") (class "Default")
      (node (ref "J16") (pin "7") (pinfunction "7_7") (pintype "passive"))
      (node (ref "U13") (pin "7") (pinfunction "O1_7") (pintype "power_in"))
    )
    (net (code "90") (name "Net-(U13-O2)") (class "Default")
      (node (ref "J16") (pin "8") (pinfunction "8_8") (pintype "passive"))
      (node (ref "U13") (pin "6") (pinfunction "O2_6") (pintype "power_in"))
    )
    (net (code "91") (name "Net-(U14-A1)") (class "Default")
      (node (ref "R26") (pin "1") (pinfunction "1_1") (pintype "passive"))
      (node (ref "U14") (pin "1") (pinfunction "A1_1") (pintype "power_in"))
    )
    (net (code "92") (name "Net-(U14-A2)") (class "Default")
      (node (ref "R29") (pin "1") (pinfunction "1_1") (pintype "passive"))
      (node (ref "U14") (pin "4") (pinfunction "A2_4") (pintype "power_in"))
    )
    (net (code "93") (name "Net-(U14-O1)") (class "Default")
      (node (ref "R27") (pin "1") (pinfunction "1_1") (pintype "passive"))
      (node (ref "U14") (pin "7") (pinfunction "O1_7") (pintype "power_in"))
    )
    (net (code "94") (name "Net-(U14-O2)") (class "Default")
      (node (ref "R28") (pin "1") (pinfunction "1_1") (pintype "passive"))
      (node (ref "U14") (pin "6") (pinfunction "O2_6") (pintype "power_in"))
    )
    (net (code "95") (name "unconnected-(J1-Pad01)") (class "Default")
      (node (ref "J1") (pin "01") (pinfunction "01_01") (pintype "passive"))
    )
    (net (code "96") (name "unconnected-(J1-Pad03)") (class "Default")
      (node (ref "J1") (pin "03") (pinfunction "03_03") (pintype "passive"))
    )
    (net (code "97") (name "unconnected-(J1-Pad05)") (class "Default")
      (node (ref "J1") (pin "05") (pinfunction "05_05") (pintype "passive"))
    )
    (net (code "98") (name "unconnected-(J1-Pad07)") (class "Default")
      (node (ref "J1") (pin "07") (pinfunction "07_07") (pintype "passive"))
    )
    (net (code "99") (name "unconnected-(J1-Pad08)") (class "Default")
      (node (ref "J1") (pin "08") (pinfunction "08_08") (pintype "passive"))
    )
    (net (code "100") (name "unconnected-(J1-Pad10)") (class "Default")
      (node (ref "J1") (pin "10") (pinfunction "10_10") (pintype "passive"))
    )
    (net (code "101") (name "unconnected-(J1-Pad12)") (class "Default")
      (node (ref "J1") (pin "12") (pinfunction "12_12") (pintype "passive"))
    )
    (net (code "102") (name "unconnected-(J1-Pad26)") (class "Default")
      (node (ref "J1") (pin "26") (pinfunction "26_26") (pintype "passive"))
    )
    (net (code "103") (name "unconnected-(J1-Pad27)") (class "Default")
      (node (ref "J1") (pin "27") (pinfunction "27_27") (pintype "passive"))
    )
    (net (code "104") (name "unconnected-(J1-Pad28)") (class "Default")
      (node (ref "J1") (pin "28") (pinfunction "28_28") (pintype "passive"))
    )
    (net (code "105") (name "unconnected-(J1-Pad38)") (class "Default")
      (node (ref "J1") (pin "38") (pinfunction "38_38") (pintype "passive"))
    )
    (net (code "106") (name "unconnected-(J7-Pad17)") (class "Default")
      (node (ref "J7") (pin "17") (pinfunction "17_17") (pintype "passive"))
    )
    (net (code "107") (name "unconnected-(J8-Pad3)") (class "Default")
      (node (ref "J8") (pin "3") (pinfunction "3_3") (pintype "passive"))
    )
    (net (code "108") (name "unconnected-(J8-Pad8)") (class "Default")
      (node (ref "J8") (pin "8") (pinfunction "8_8") (pintype "passive"))
    )
    (net (code "109") (name "unconnected-(J8-Pad9)") (class "Default")
      (node (ref "J8") (pin "9") (pinfunction "9_9") (pintype "passive"))
    )
    (net (code "110") (name "unconnected-(J8-Pad10)") (class "Default")
      (node (ref "J8") (pin "10") (pinfunction "10_10") (pintype "passive"))
    )
    (net (code "111") (name "unconnected-(J8-Pad11)") (class "Default")
      (node (ref "J8") (pin "11") (pinfunction "11_11") (pintype "passive"))
    )
    (net (code "112") (name "unconnected-(J8-Pad12)") (class "Default")
      (node (ref "J8") (pin "12") (pinfunction "12_12") (pintype "passive"))
    )
    (net (code "113") (name "unconnected-(J8-Pad13)") (class "Default")
      (node (ref "J8") (pin "13") (pinfunction "13_13") (pintype "passive"))
    )
    (net (code "114") (name "unconnected-(J8-Pad15)") (class "Default")
      (node (ref "J8") (pin "15") (pinfunction "15_15") (pintype "passive"))
    )
    (net (code "115") (name "unconnected-(J8-Pad16)") (class "Default")
      (node (ref "J8") (pin "16") (pinfunction "16_16") (pintype "passive"))
    )
    (net (code "116") (name "unconnected-(J8-Pad17)") (class "Default")
      (node (ref "J8") (pin "17") (pinfunction "17_17") (pintype "passive"))
    )
    (net (code "117") (name "unconnected-(J8-Pad18)") (class "Default")
      (node (ref "J8") (pin "18") (pinfunction "18_18") (pintype "passive"))
    )
    (net (code "118") (name "unconnected-(J8-Pad19)") (class "Default")
      (node (ref "J8") (pin "19") (pinfunction "19_19") (pintype "passive"))
    )
    (net (code "119") (name "unconnected-(J8-Pad22)") (class "Default")
      (node (ref "J8") (pin "22") (pinfunction "22_22") (pintype "passive"))
    )
    (net (code "120") (name "unconnected-(J8-Pad23)") (class "Default")
      (node (ref "J8") (pin "23") (pinfunction "23_23") (pintype "passive"))
    )
    (net (code "121") (name "unconnected-(J8-Pad24)") (class "Default")
      (node (ref "J8") (pin "24") (pinfunction "24_24") (pintype "passive"))
    )
    (net (code "122") (name "unconnected-(J9-Pad6)") (class "Default")
      (node (ref "J9") (pin "6") (pinfunction "6_6") (pintype "passive"))
    )
    (net (code "123") (name "unconnected-(J9-Pad7)") (class "Default")
      (node (ref "J9") (pin "7") (pinfunction "7_7") (pintype "passive"))
    )
    (net (code "124") (name "unconnected-(J9-Pad8)") (class "Default")
      (node (ref "J9") (pin "8") (pinfunction "8_8") (pintype "passive"))
    )
    (net (code "125") (name "unconnected-(J9-Pad9)") (class "Default")
      (node (ref "J9") (pin "9") (pinfunction "9_9") (pintype "passive"))
    )
    (net (code "126") (name "unconnected-(J10-Pad6)") (class "Default")
      (node (ref "J10") (pin "6") (pinfunction "6_6") (pintype "passive"))
    )
    (net (code "127") (name "unconnected-(J10-Pad7)") (class "Default")
      (node (ref "J10") (pin "7") (pinfunction "7_7") (pintype "passive"))
    )
    (net (code "128") (name "unconnected-(J10-Pad8)") (class "Default")
      (node (ref "J10") (pin "8") (pinfunction "8_8") (pintype "passive"))
    )
    (net (code "129") (name "unconnected-(J10-Pad9)") (class "Default")
      (node (ref "J10") (pin "9") (pinfunction "9_9") (pintype "passive"))
    )
    (net (code "130") (name "unconnected-(J15-Pad1)") (class "Default")
      (node (ref "J15") (pin "1") (pinfunction "1_1") (pintype "passive"))
    )
    (net (code "131") (name "unconnected-(PS1-NC-Pad8)") (class "Default")
      (node (ref "PS1") (pin "8") (pinfunction "NC_8") (pintype "passive"))
    )
    (net (code "132") (name "unconnected-(U5-A2-Pad4)") (class "Default")
      (node (ref "U5") (pin "4") (pinfunction "A2_4") (pintype "power_in"))
    )
    (net (code "133") (name "unconnected-(U5-C2-Pad3)") (class "Default")
      (node (ref "U5") (pin "3") (pinfunction "C2_3") (pintype "power_in"))
    )
    (net (code "134") (name "unconnected-(U5-O2-Pad6)") (class "Default")
      (node (ref "U5") (pin "6") (pinfunction "O2_6") (pintype "power_in"))
    )
  )
)
